# C2_from_parallel_port.net
KiCad netlist of a schematic drawn in EAGLE
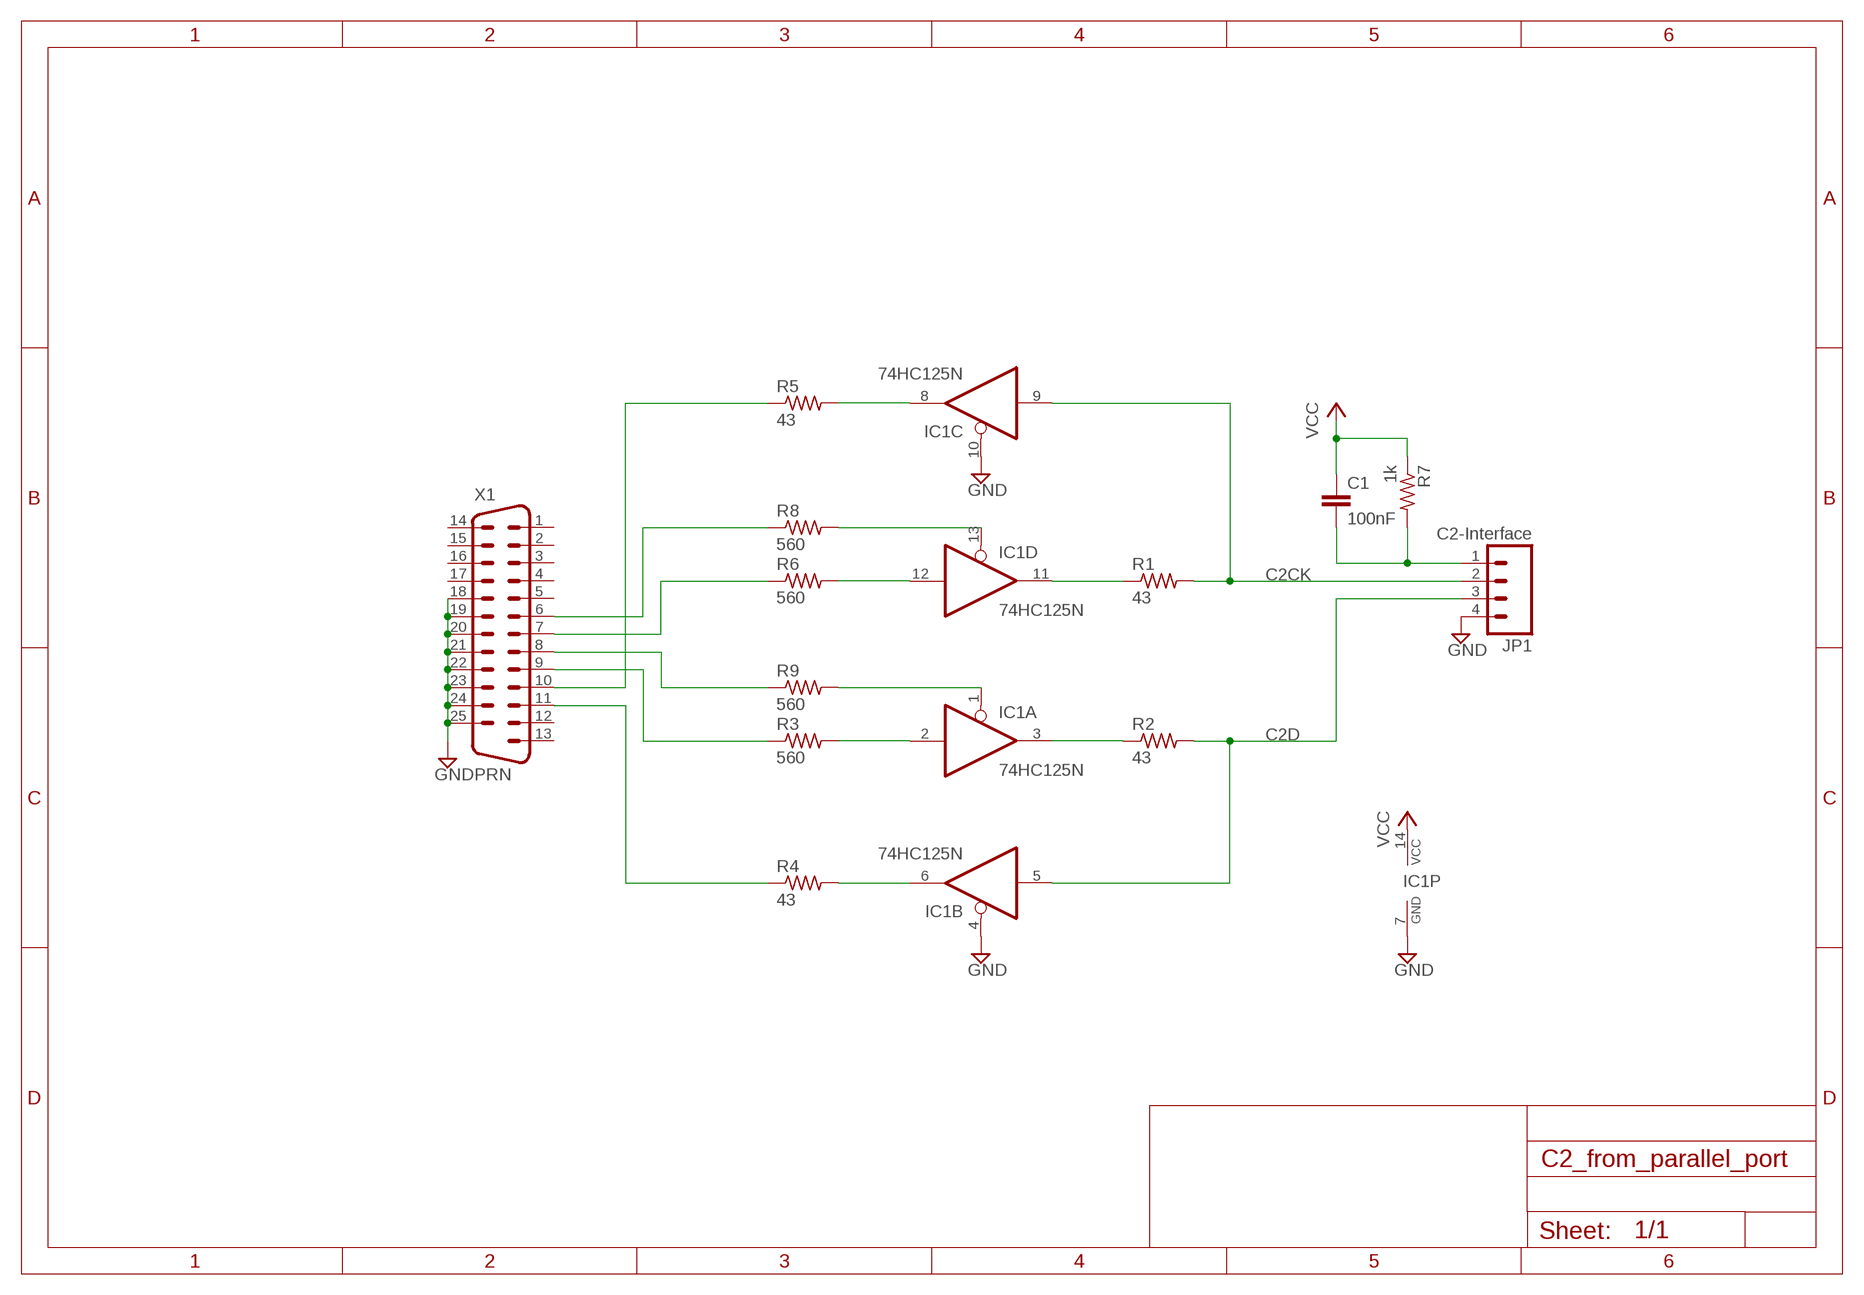
[diagram p0: schematic, sheet 1]

(export (version "E")
  (design (tool "Eeschema 10.0.6"))
  (components
    (comp (ref "C1")
      (value "100nF")
      (footprint "eagle-import:RCL_C050-025X075")
      (libsource (lib "eagle-import") (part "RCL_C-EU050-025X075"))
    )
    (comp (ref "IC1")
      (value "74HC125N")
      (footprint "eagle-import:DIL14")
      (libsource (lib "eagle-import") (part "74125NHC"))
    )
    (comp (ref "JP1")
      (value "C2-Interface")
      (footprint "eagle-import:MOLEX-1X4")
      (libsource (lib "eagle-import") (part "M04POLAR"))
    )
    (comp (ref "R1")
      (value "43")
      (footprint "eagle-import:RCL_0204V")
      (libsource (lib "eagle-import") (part "RCL_R-US_0204/2V"))
    )
    (comp (ref "R2")
      (value "43")
      (footprint "eagle-import:RCL_0204V")
      (libsource (lib "eagle-import") (part "RCL_R-US_0204/2V"))
    )
    (comp (ref "R3")
      (value "560")
      (footprint "eagle-import:RCL_0204V")
      (libsource (lib "eagle-import") (part "RCL_R-US_0204/2V"))
    )
    (comp (ref "R4")
      (value "43")
      (footprint "eagle-import:RCL_0204V")
      (libsource (lib "eagle-import") (part "RCL_R-US_0204/2V"))
    )
    (comp (ref "R5")
      (value "43")
      (footprint "eagle-import:RCL_0204V")
      (libsource (lib "eagle-import") (part "RCL_R-US_0204/2V"))
    )
    (comp (ref "R6")
      (value "560")
      (footprint "eagle-import:RCL_0204V")
      (libsource (lib "eagle-import") (part "RCL_R-US_0204/2V"))
    )
    (comp (ref "R7")
      (value "1k")
      (footprint "eagle-import:RCL_0204V")
      (libsource (lib "eagle-import") (part "RCL_R-US_0204/2V"))
    )
    (comp (ref "R8")
      (value "560")
      (footprint "eagle-import:RCL_0204V")
      (libsource (lib "eagle-import") (part "RCL_R-US_0204/2V"))
    )
    (comp (ref "R9")
      (value "560")
      (footprint "eagle-import:RCL_0204V")
      (libsource (lib "eagle-import") (part "RCL_R-US_0204/2V"))
    )
    (comp (ref "X1")
      (value "PRN")
      (footprint "eagle-import:M25D")
      (libsource (lib "eagle-import") (part "DB25D"))
    )
  )
  (nets
    (net (code "1") (name "/C2CK") (class "Default")
      (node (ref "IC1") (pin "9") (pinfunction "I_9") (pintype "input"))
      (node (ref "JP1") (pin "2") (pinfunction "2_2") (pintype "passive"))
      (node (ref "R1") (pin "2") (pinfunction "2_2") (pintype "passive"))
    )
    (net (code "2") (name "/C2D") (class "Default")
      (node (ref "IC1") (pin "5") (pinfunction "I_5") (pintype "input"))
      (node (ref "JP1") (pin "3") (pinfunction "3_3") (pintype "passive"))
      (node (ref "R2") (pin "2") (pinfunction "2_2") (pintype "passive"))
    )
    (net (code "3") (name "GND") (class "Default")
      (node (ref "IC1") (pin "10") (pinfunction "OE_10") (pintype "input"))
      (node (ref "IC1") (pin "4") (pinfunction "OE_4") (pintype "input"))
      (node (ref "IC1") (pin "7") (pinfunction "GND_7") (pintype "power_in"))
      (node (ref "JP1") (pin "4") (pinfunction "4_4") (pintype "passive"))
      (node (ref "X1") (pin "18") (pinfunction "18_18") (pintype "passive"))
      (node (ref "X1") (pin "19") (pinfunction "19_19") (pintype "passive"))
      (node (ref "X1") (pin "20") (pinfunction "20_20") (pintype "passive"))
      (node (ref "X1") (pin "21") (pinfunction "21_21") (pintype "passive"))
      (node (ref "X1") (pin "22") (pinfunction "22_22") (pintype "passive"))
      (node (ref "X1") (pin "23") (pinfunction "23_23") (pintype "passive"))
      (node (ref "X1") (pin "24") (pinfunction "24_24") (pintype "passive"))
      (node (ref "X1") (pin "25") (pinfunction "25_25") (pintype "passive"))
    )
    (net (code "4") (name "Net-(C1-Pad2)") (class "Default")
      (node (ref "C1") (pin "2") (pinfunction "2_2") (pintype "passive"))
      (node (ref "JP1") (pin "1") (pinfunction "1_1") (pintype "passive"))
      (node (ref "R7") (pin "2") (pinfunction "2_2") (pintype "passive"))
    )
    (net (code "5") (name "Net-(IC1A-I)") (class "Default")
      (node (ref "IC1") (pin "2") (pinfunction "I_2") (pintype "input"))
      (node (ref "R3") (pin "2") (pinfunction "2_2") (pintype "passive"))
    )
    (net (code "6") (name "Net-(IC1A-O)") (class "Default")
      (node (ref "IC1") (pin "3") (pinfunction "O_3") (pintype "tri_state"))
      (node (ref "R2") (pin "1") (pinfunction "1_1") (pintype "passive"))
    )
    (net (code "7") (name "Net-(IC1A-OE)") (class "Default")
      (node (ref "IC1") (pin "1") (pinfunction "OE_1") (pintype "input"))
      (node (ref "R9") (pin "2") (pinfunction "2_2") (pintype "passive"))
    )
    (net (code "8") (name "Net-(IC1B-O)") (class "Default")
      (node (ref "IC1") (pin "6") (pinfunction "O_6") (pintype "tri_state"))
      (node (ref "R4") (pin "2") (pinfunction "2_2") (pintype "passive"))
    )
    (net (code "9") (name "Net-(IC1C-O)") (class "Default")
      (node (ref "IC1") (pin "8") (pinfunction "O_8") (pintype "tri_state"))
      (node (ref "R5") (pin "2") (pinfunction "2_2") (pintype "passive"))
    )
    (net (code "10") (name "Net-(IC1D-I)") (class "Default")
      (node (ref "IC1") (pin "12") (pinfunction "I_12") (pintype "input"))
      (node (ref "R6") (pin "2") (pinfunction "2_2") (pintype "passive"))
    )
    (net (code "11") (name "Net-(IC1D-O)") (class "Default")
      (node (ref "IC1") (pin "11") (pinfunction "O_11") (pintype "tri_state"))
      (node (ref "R1") (pin "1") (pinfunction "1_1") (pintype "passive"))
    )
    (net (code "12") (name "Net-(IC1D-OE)") (class "Default")
      (node (ref "IC1") (pin "13") (pinfunction "OE_13") (pintype "input"))
      (node (ref "R8") (pin "2") (pinfunction "2_2") (pintype "passive"))
    )
    (net (code "13") (name "Net-(R3-Pad1)") (class "Default")
      (node (ref "R3") (pin "1") (pinfunction "1_1") (pintype "passive"))
      (node (ref "X1") (pin "9") (pinfunction "9_9") (pintype "passive"))
    )
    (net (code "14") (name "Net-(R4-Pad1)") (class "Default")
      (node (ref "R4") (pin "1") (pinfunction "1_1") (pintype "passive"))
      (node (ref "X1") (pin "11") (pinfunction "11_11") (pintype "passive"))
    )
    (net (code "15") (name "Net-(R5-Pad1)") (class "Default")
      (node (ref "R5") (pin "1") (pinfunction "1_1") (pintype "passive"))
      (node (ref "X1") (pin "10") (pinfunction "10_10") (pintype "passive"))
    )
    (net (code "16") (name "Net-(R6-Pad1)") (class "Default")
      (node (ref "R6") (pin "1") (pinfunction "1_1") (pintype "passive"))
      (node (ref "X1") (pin "7") (pinfunction "7_7") (pintype "passive"))
    )
    (net (code "17") (name "Net-(R8-Pad1)") (class "Default")
      (node (ref "R8") (pin "1") (pinfunction "1_1") (pintype "passive"))
      (node (ref "X1") (pin "6") (pinfunction "6_6") (pintype "passive"))
    )
    (net (code "18") (name "Net-(R9-Pad1)") (class "Default")
      (node (ref "R9") (pin "1") (pinfunction "1_1") (pintype "passive"))
      (node (ref "X1") (pin "8") (pinfunction "8_8") (pintype "passive"))
    )
    (net (code "19") (name "VCC") (class "Default")
      (node (ref "C1") (pin "1") (pinfunction "1_1") (pintype "passive"))
      (node (ref "IC1") (pin "14") (pinfunction "VCC_14") (pintype "power_in"))
      (node (ref "R7") (pin "1") (pinfunction "1_1") (pintype "passive"))
    )
    (net (code "20") (name "unconnected-(X1-Pad1)") (class "Default")
      (node (ref "X1") (pin "1") (pinfunction "1_1") (pintype "passive"))
    )
    (net (code "21") (name "unconnected-(X1-Pad2)") (class "Default")
      (node (ref "X1") (pin "2") (pinfunction "2_2") (pintype "passive"))
    )
    (net (code "22") (name "unconnected-(X1-Pad3)") (class "Default")
      (node (ref "X1") (pin "3") (pinfunction "3_3") (pintype "passive"))
    )
    (net (code "23") (name "unconnected-(X1-Pad4)") (class "Default")
      (node (ref "X1") (pin "4") (pinfunction "4_4") (pintype "passive"))
    )
    (net (code "24") (name "unconnected-(X1-Pad5)") (class "Default")
      (node (ref "X1") (pin "5") (pinfunction "5_5") (pintype "passive"))
    )
    (net (code "25") (name "unconnected-(X1-Pad12)") (class "Default")
      (node (ref "X1") (pin "12") (pinfunction "12_12") (pintype "passive"))
    )
    (net (code "26") (name "unconnected-(X1-Pad13)") (class "Default")
      (node (ref "X1") (pin "13") (pinfunction "13_13") (pintype "passive"))
    )
    (net (code "27") (name "unconnected-(X1-Pad14)") (class "Default")
      (node (ref "X1") (pin "14") (pinfunction "14_14") (pintype "passive"))
    )
    (net (code "28") (name "unconnected-(X1-Pad15)") (class "Default")
      (node (ref "X1") (pin "15") (pinfunction "15_15") (pintype "passive"))
    )
    (net (code "29") (name "unconnected-(X1-Pad16)") (class "Default")
      (node (ref "X1") (pin "16") (pinfunction "16_16") (pintype "passive"))
    )
    (net (code "30") (name "unconnected-(X1-Pad17)") (class "Default")
      (node (ref "X1") (pin "17") (pinfunction "17_17") (pintype "passive"))
    )
  )
)
